# working.net
KiCad netlist of a schematic drawn in EAGLE
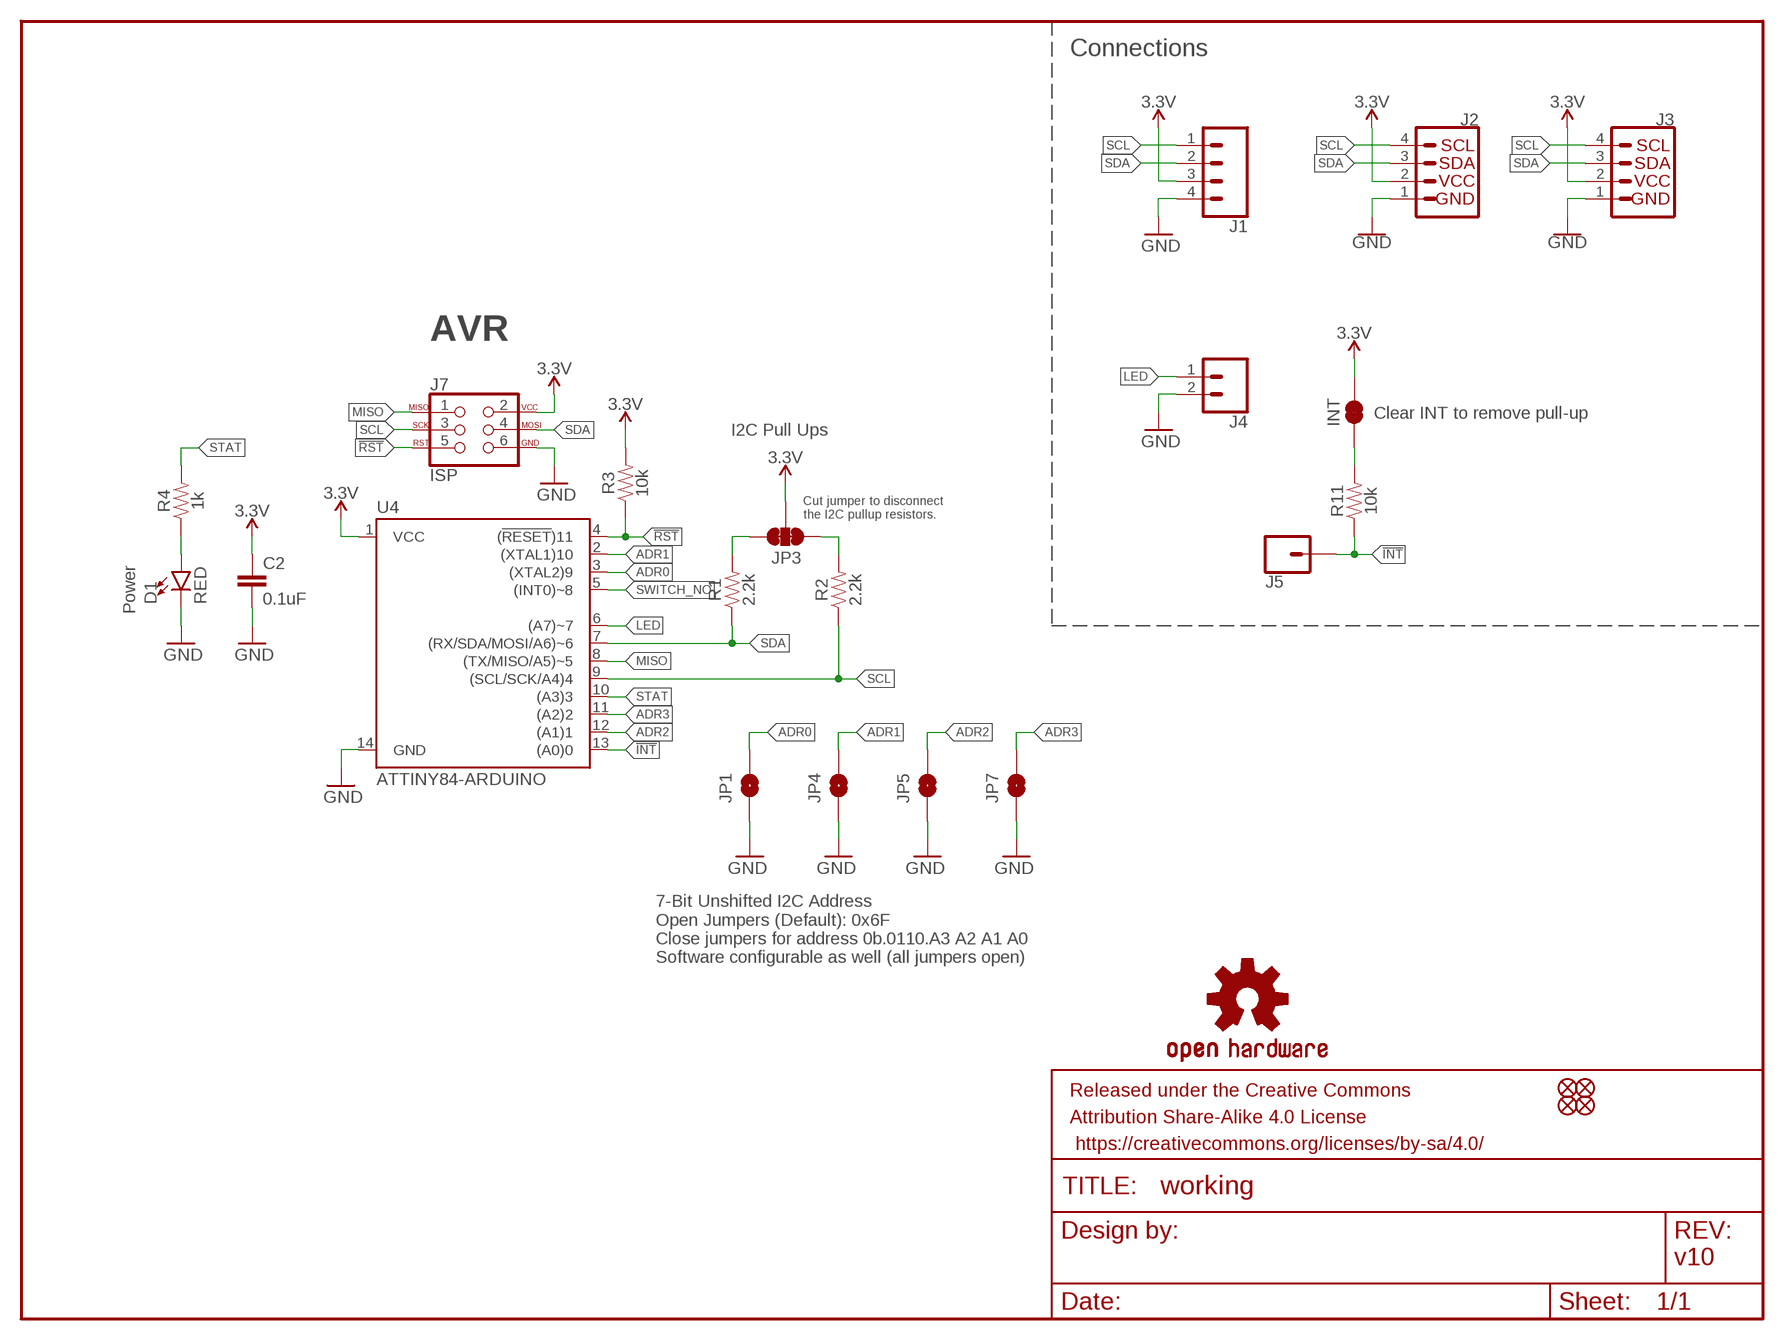
[diagram p0: schematic, sheet 1]

(export (version "E")
  (design (tool "Eeschema 10.0.6"))
  (components
    (comp (ref "C2")
      (value "0.1uF")
      (footprint "eagle-import:0603")
      (libsource (lib "eagle-import") (part "0.1UF-0603-25V-(+80/-20%)"))
    )
    (comp (ref "D1")
      (value "RED")
      (footprint "eagle-import:LED-0603")
      (libsource (lib "eagle-import") (part "LED-RED0603"))
    )
    (comp (ref "FRAME1")
      (value "FRAME-LETTER")
      (footprint "eagle-import:CREATIVE_COMMONS")
      (libsource (lib "eagle-import") (part "FRAME-LETTER"))
    )
    (comp (ref "INT")
      (value "JUMPER-SMT_2_NC_TRACE_SILK")
      (footprint "eagle-import:SMT-JUMPER_2_NC_TRACE_SILK")
      (libsource (lib "eagle-import") (part "JUMPER-SMT_2_NC_TRACE_SILK"))
    )
    (comp (ref "J1")
      (value "CONN_041X04_NO_SILK")
      (footprint "eagle-import:1X04_NO_SILK")
      (libsource (lib "eagle-import") (part "CONN_041X04_NO_SILK"))
    )
    (comp (ref "J2")
      (value "QWIIC_CONNECTORJS-1MM")
      (footprint "eagle-import:JST04_1MM_RA")
      (libsource (lib "eagle-import") (part "QWIIC_CONNECTORJS-1MM"))
    )
    (comp (ref "J3")
      (value "QWIIC_CONNECTORJS-1MM")
      (footprint "eagle-import:JST04_1MM_RA")
      (libsource (lib "eagle-import") (part "QWIIC_CONNECTORJS-1MM"))
    )
    (comp (ref "J4")
      (value "CONN_021X02_NO_SILK")
      (footprint "eagle-import:1X02_NO_SILK")
      (libsource (lib "eagle-import") (part "CONN_021X02_NO_SILK"))
    )
    (comp (ref "J5")
      (value "CONN_01PTH_NO_SILK_YES_STOP")
      (footprint "eagle-import:1X01_NO_SILK")
      (libsource (lib "eagle-import") (part "CONN_01PTH_NO_SILK_YES_STOP"))
    )
    (comp (ref "J7")
      (value "ISP")
      (footprint "eagle-import:2X3_TEST_POINTS")
      (libsource (lib "eagle-import") (part "AVR_SPI_PROG_3X2TESTPOINTS"))
    )
    (comp (ref "JP1")
      (value "JUMPER-SMT_2_NO_SILK")
      (footprint "eagle-import:SMT-JUMPER_2_NO_SILK")
      (libsource (lib "eagle-import") (part "JUMPER-SMT_2_NO_SILK"))
    )
    (comp (ref "JP2")
      (value "FIDUCIALUFIDUCIAL")
      (footprint "eagle-import:MICRO-FIDUCIAL")
      (libsource (lib "eagle-import") (part "FIDUCIALUFIDUCIAL"))
    )
    (comp (ref "JP3")
      (value "JUMPER-SMT_3_2-NC_TRACE_SILK")
      (footprint "eagle-import:SMT-JUMPER_3_2-NC_TRACE_SILK")
      (libsource (lib "eagle-import") (part "JUMPER-SMT_3_2-NC_TRACE_SILK"))
    )
    (comp (ref "JP4")
      (value "JUMPER-SMT_2_NO_SILK")
      (footprint "eagle-import:SMT-JUMPER_2_NO_SILK")
      (libsource (lib "eagle-import") (part "JUMPER-SMT_2_NO_SILK"))
    )
    (comp (ref "JP5")
      (value "JUMPER-SMT_2_NO_SILK")
      (footprint "eagle-import:SMT-JUMPER_2_NO_SILK")
      (libsource (lib "eagle-import") (part "JUMPER-SMT_2_NO_SILK"))
    )
    (comp (ref "JP6")
      (value "FIDUCIALUFIDUCIAL")
      (footprint "eagle-import:MICRO-FIDUCIAL")
      (libsource (lib "eagle-import") (part "FIDUCIALUFIDUCIAL"))
    )
    (comp (ref "JP7")
      (value "JUMPER-SMT_2_NO_SILK")
      (footprint "eagle-import:SMT-JUMPER_2_NO_SILK")
      (libsource (lib "eagle-import") (part "JUMPER-SMT_2_NO_SILK"))
    )
    (comp (ref "JP8")
      (value "FIDUCIALUFIDUCIAL")
      (footprint "eagle-import:MICRO-FIDUCIAL")
      (libsource (lib "eagle-import") (part "FIDUCIALUFIDUCIAL"))
    )
    (comp (ref "JP9")
      (value "FIDUCIALUFIDUCIAL")
      (footprint "eagle-import:MICRO-FIDUCIAL")
      (libsource (lib "eagle-import") (part "FIDUCIALUFIDUCIAL"))
    )
    (comp (ref "LOGO1")
      (value "OSHW-LOGOMINI")
      (footprint "eagle-import:OSHW-LOGO-MINI")
      (libsource (lib "eagle-import") (part "OSHW-LOGOMINI"))
    )
    (comp (ref "R1")
      (value "2.2k")
      (footprint "eagle-import:0603")
      (libsource (lib "eagle-import") (part "2.2KOHM-0603-1/10W-1%"))
    )
    (comp (ref "R2")
      (value "2.2k")
      (footprint "eagle-import:0603")
      (libsource (lib "eagle-import") (part "2.2KOHM-0603-1/10W-1%"))
    )
    (comp (ref "R3")
      (value "10k")
      (footprint "eagle-import:0603")
      (libsource (lib "eagle-import") (part "10KOHM-0603-1/10W-1%"))
    )
    (comp (ref "R4")
      (value "1k")
      (footprint "eagle-import:0603")
      (libsource (lib "eagle-import") (part "1KOHM-0603-1/10W-1%"))
    )
    (comp (ref "R11")
      (value "10k")
      (footprint "eagle-import:0603")
      (libsource (lib "eagle-import") (part "10KOHM-0603-1/10W-1%"))
    )
    (comp (ref "U4")
      (value "ATTINY84-ARDUINO")
      (footprint "eagle-import:SO14")
      (libsource (lib "eagle-import") (part "ATTINY84-ARDUINO"))
    )
  )
  (nets
    (net (code "1") (name "/~{INT}") (class "Default")
      (node (ref "J5") (pin "1") (pinfunction "1_1") (pintype "passive"))
      (node (ref "R11") (pin "1") (pinfunction "1_1") (pintype "passive"))
      (node (ref "U4") (pin "13") (pinfunction "(A0)0_13") (pintype "bidirectional"))
    )
    (net (code "2") (name "/~{RST}") (class "Default")
      (node (ref "J7") (pin "5") (pinfunction "5_5") (pintype "passive"))
      (node (ref "R3") (pin "1") (pinfunction "1_1") (pintype "passive"))
      (node (ref "U4") (pin "4") (pinfunction "(~{RESET})11_4") (pintype "bidirectional"))
    )
    (net (code "3") (name "3.3V") (class "Default")
      (node (ref "C2") (pin "1") (pinfunction "1_1") (pintype "passive"))
      (node (ref "INT") (pin "2") (pinfunction "2_2") (pintype "passive"))
      (node (ref "J1") (pin "3") (pinfunction "3_3") (pintype "passive"))
      (node (ref "J2") (pin "2") (pinfunction "2_2") (pintype "power_in"))
      (node (ref "J3") (pin "2") (pinfunction "2_2") (pintype "power_in"))
      (node (ref "J7") (pin "2") (pinfunction "2_2") (pintype "passive"))
      (node (ref "JP3") (pin "2") (pinfunction "2_2") (pintype "passive"))
      (node (ref "R3") (pin "2") (pinfunction "2_2") (pintype "passive"))
      (node (ref "U4") (pin "1") (pinfunction "VCC_1") (pintype "bidirectional"))
    )
    (net (code "4") (name "ADR0") (class "Default")
      (node (ref "JP1") (pin "2") (pinfunction "2_2") (pintype "passive"))
      (node (ref "U4") (pin "3") (pinfunction "(XTAL2)9_3") (pintype "bidirectional"))
    )
    (net (code "5") (name "ADR1") (class "Default")
      (node (ref "JP4") (pin "2") (pinfunction "2_2") (pintype "passive"))
      (node (ref "U4") (pin "2") (pinfunction "(XTAL1)10_2") (pintype "bidirectional"))
    )
    (net (code "6") (name "ADR2") (class "Default")
      (node (ref "JP5") (pin "2") (pinfunction "2_2") (pintype "passive"))
      (node (ref "U4") (pin "12") (pinfunction "(A1)1_12") (pintype "bidirectional"))
    )
    (net (code "7") (name "ADR3") (class "Default")
      (node (ref "JP7") (pin "2") (pinfunction "2_2") (pintype "passive"))
      (node (ref "U4") (pin "11") (pinfunction "(A2)2_11") (pintype "bidirectional"))
    )
    (net (code "8") (name "GND") (class "Default")
      (node (ref "C2") (pin "2") (pinfunction "2_2") (pintype "passive"))
      (node (ref "D1") (pin "C") (pinfunction "C_C") (pintype "passive"))
      (node (ref "J1") (pin "4") (pinfunction "4_4") (pintype "passive"))
      (node (ref "J2") (pin "1") (pinfunction "1_1") (pintype "power_in"))
      (node (ref "J3") (pin "1") (pinfunction "1_1") (pintype "power_in"))
      (node (ref "J4") (pin "2") (pinfunction "2_2") (pintype "passive"))
      (node (ref "J7") (pin "6") (pinfunction "6_6") (pintype "passive"))
      (node (ref "JP1") (pin "1") (pinfunction "1_1") (pintype "passive"))
      (node (ref "JP4") (pin "1") (pinfunction "1_1") (pintype "passive"))
      (node (ref "JP5") (pin "1") (pinfunction "1_1") (pintype "passive"))
      (node (ref "JP7") (pin "1") (pinfunction "1_1") (pintype "passive"))
      (node (ref "U4") (pin "14") (pinfunction "GND_14") (pintype "bidirectional"))
    )
    (net (code "9") (name "LED") (class "Default")
      (node (ref "J4") (pin "1") (pinfunction "1_1") (pintype "passive"))
      (node (ref "U4") (pin "6") (pinfunction "(A7)~{7}_6") (pintype "bidirectional"))
    )
    (net (code "10") (name "MISO") (class "Default")
      (node (ref "J7") (pin "1") (pinfunction "1_1") (pintype "passive"))
      (node (ref "U4") (pin "8") (pinfunction "(TX/MISO/A5)~{5}_8") (pintype "bidirectional"))
    )
    (net (code "11") (name "Net-(D1-PadA)") (class "Default")
      (node (ref "D1") (pin "A") (pinfunction "A_A") (pintype "passive"))
      (node (ref "R4") (pin "1") (pinfunction "1_1") (pintype "passive"))
    )
    (net (code "12") (name "Net-(INT-Pad1)") (class "Default")
      (node (ref "INT") (pin "1") (pinfunction "1_1") (pintype "passive"))
      (node (ref "R11") (pin "2") (pinfunction "2_2") (pintype "passive"))
    )
    (net (code "13") (name "Net-(JP3-Pad1)") (class "Default")
      (node (ref "JP3") (pin "1") (pinfunction "1_1") (pintype "passive"))
      (node (ref "R2") (pin "2") (pinfunction "2_2") (pintype "passive"))
    )
    (net (code "14") (name "Net-(JP3-Pad3)") (class "Default")
      (node (ref "JP3") (pin "3") (pinfunction "3_3") (pintype "passive"))
      (node (ref "R1") (pin "2") (pinfunction "2_2") (pintype "passive"))
    )
    (net (code "15") (name "SCL") (class "Default")
      (node (ref "J1") (pin "1") (pinfunction "1_1") (pintype "passive"))
      (node (ref "J2") (pin "4") (pinfunction "4_4") (pintype "passive"))
      (node (ref "J3") (pin "4") (pinfunction "4_4") (pintype "passive"))
      (node (ref "J7") (pin "3") (pinfunction "3_3") (pintype "passive"))
      (node (ref "R2") (pin "1") (pinfunction "1_1") (pintype "passive"))
      (node (ref "U4") (pin "9") (pinfunction "(SCL/SCK/A4)4_9") (pintype "bidirectional"))
    )
    (net (code "16") (name "SDA") (class "Default")
      (node (ref "J1") (pin "2") (pinfunction "2_2") (pintype "passive"))
      (node (ref "J2") (pin "3") (pinfunction "3_3") (pintype "passive"))
      (node (ref "J3") (pin "3") (pinfunction "3_3") (pintype "passive"))
      (node (ref "J7") (pin "4") (pinfunction "4_4") (pintype "passive"))
      (node (ref "R1") (pin "1") (pinfunction "1_1") (pintype "passive"))
      (node (ref "U4") (pin "7") (pinfunction "(RX/SDA/MOSI/A6)~{6}_7") (pintype "bidirectional"))
    )
    (net (code "17") (name "STAT") (class "Default")
      (node (ref "R4") (pin "2") (pinfunction "2_2") (pintype "passive"))
      (node (ref "U4") (pin "10") (pinfunction "(A3)3_10") (pintype "bidirectional"))
    )
    (net (code "18") (name "SWITCH_NO") (class "Default")
      (node (ref "U4") (pin "5") (pinfunction "(INT0)~{8}_5") (pintype "bidirectional"))
    )
  )
)
